# UM_LMA.net
KiCad netlist of a schematic drawn in EAGLE
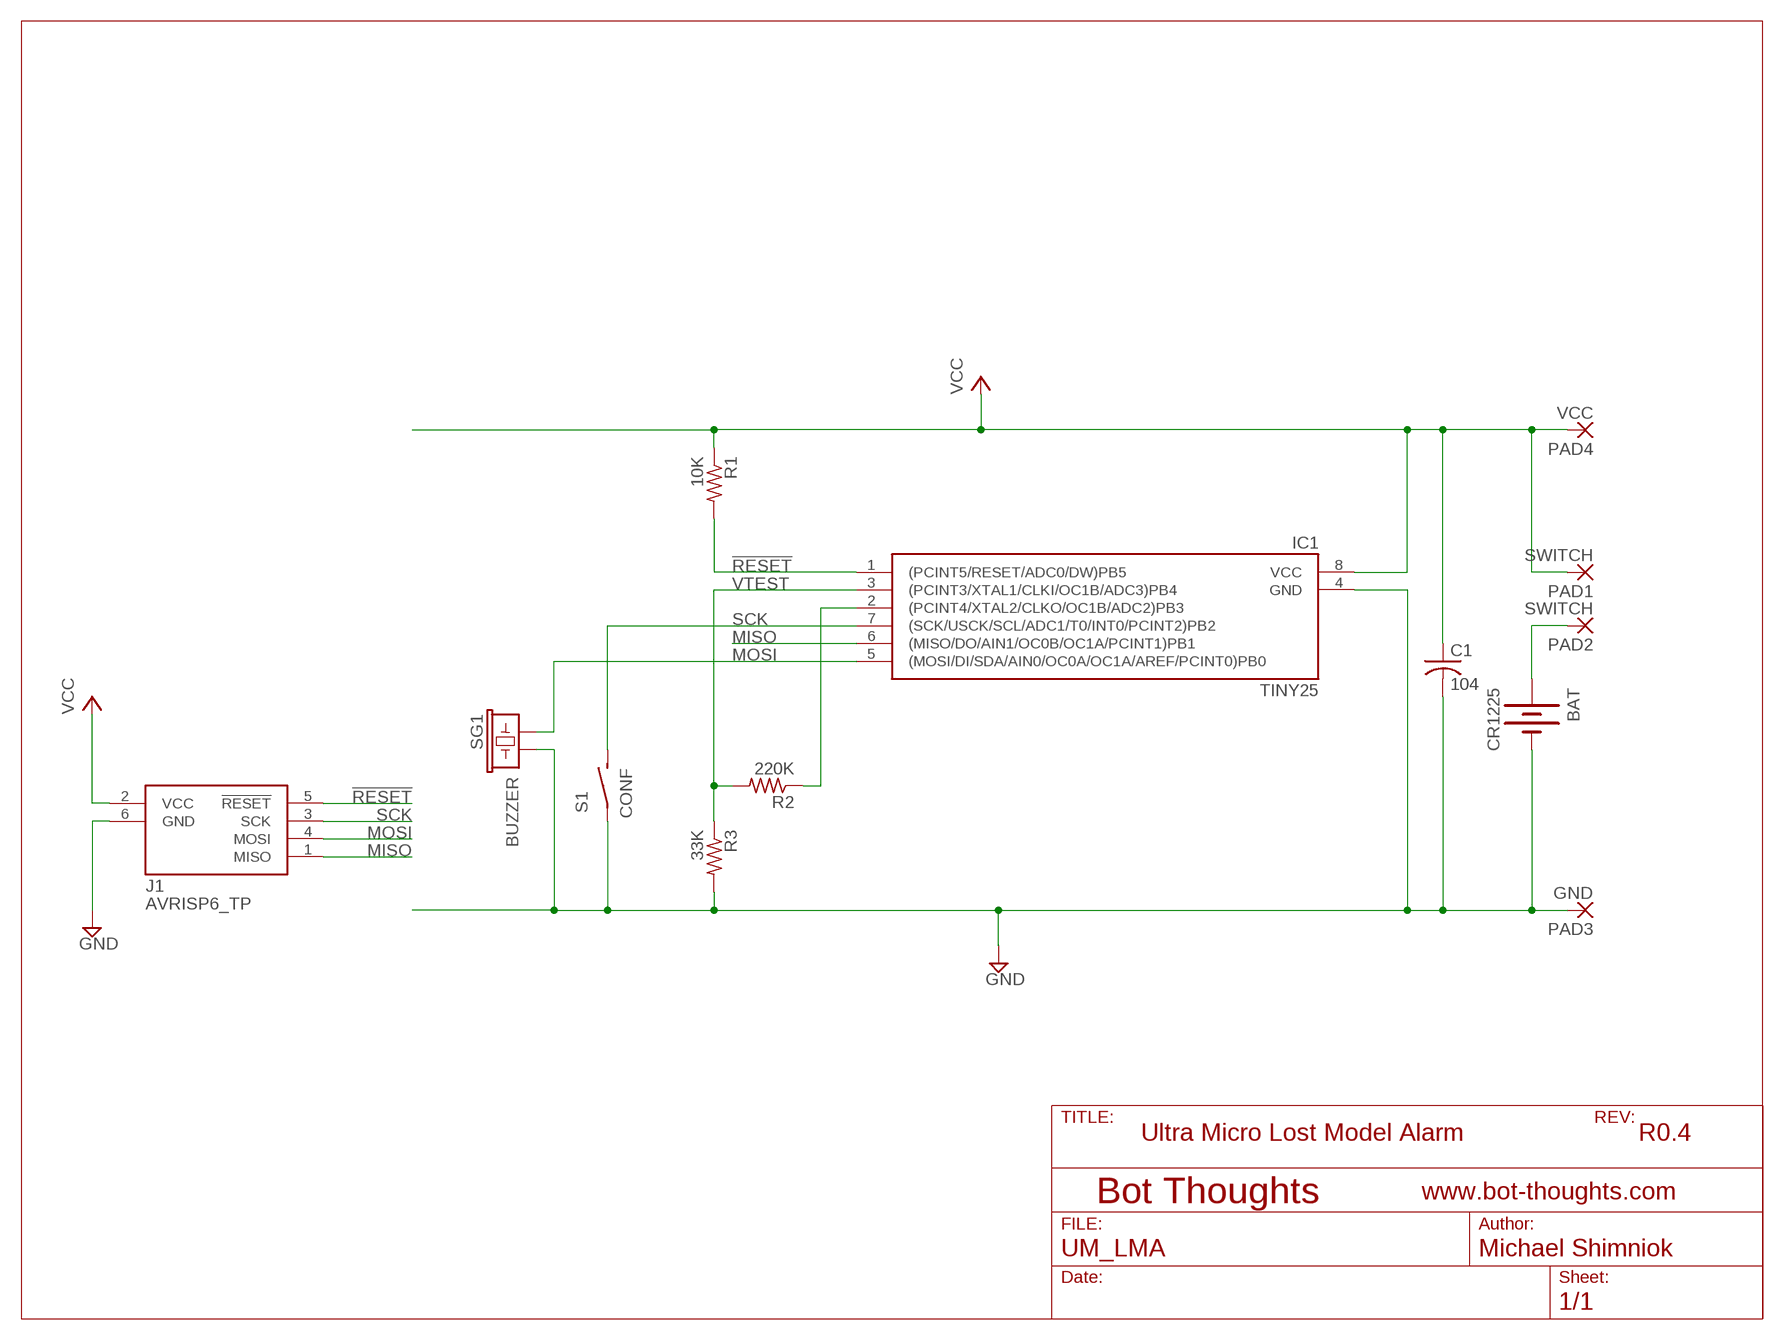
[diagram p0: schematic, sheet 1]

(export (version "E")
  (design (tool "Eeschema 10.0.6"))
  (components
    (comp (ref "BAT")
      (value "CR1225")
      (footprint "eagle-import:BATTCON_12MM_PTH")
      (libsource (lib "eagle-import") (part "BATTERY12PTH"))
    )
    (comp (ref "C1")
      (value "104")
      (footprint "eagle-import:C0603K")
      (fields (field (name "PARTNO") "GRM188R60J105KA01D"))
      (libsource (lib "eagle-import") (part "C-USC0603K"))
    )
    (comp (ref "IC1")
      (value "TINY25")
      (footprint "eagle-import:SOIC8N")
      (libsource (lib "eagle-import") (part "TINY25-20SSU"))
    )
    (comp (ref "J1")
      (value "AVRISP6_TP")
      (footprint "eagle-import:2X3_TP")
      (libsource (lib "eagle-import") (part "AVRISP6_TP"))
    )
    (comp (ref "PAD1")
      (value "SWITCH")
      (footprint "eagle-import:1,6_0,8")
      (libsource (lib "eagle-import") (part "WIREPAD1,6/0,8"))
    )
    (comp (ref "PAD2")
      (value "SWITCH")
      (footprint "eagle-import:1,6_0,8")
      (libsource (lib "eagle-import") (part "WIREPAD1,6/0,8"))
    )
    (comp (ref "PAD3")
      (value "GND")
      (footprint "eagle-import:1,6_0,8")
      (libsource (lib "eagle-import") (part "WIREPAD1,6/0,8"))
    )
    (comp (ref "PAD4")
      (value "VCC")
      (footprint "eagle-import:1,6_0,8")
      (libsource (lib "eagle-import") (part "WIREPAD1,6/0,8"))
    )
    (comp (ref "R1")
      (value "10K")
      (footprint "eagle-import:R0603")
      (fields (field (name "PARTNO") "ERJ-3GEYJ102V"))
      (libsource (lib "eagle-import") (part "R-US_R0603"))
    )
    (comp (ref "R2")
      (value "220K")
      (footprint "eagle-import:R0603")
      (fields (field (name "PARTNO") "ERJ-3GEYJ102V"))
      (libsource (lib "eagle-import") (part "R-US_R0603"))
    )
    (comp (ref "R3")
      (value "33K")
      (footprint "eagle-import:R0603")
      (fields (field (name "PARTNO") "ERJ-3GEYJ102V"))
      (libsource (lib "eagle-import") (part "R-US_R0603"))
    )
    (comp (ref "S1")
      (value "CONF")
      (footprint "eagle-import:3X4X2TACT")
      (libsource (lib "eagle-import") (part "SPST_3X4X2"))
    )
    (comp (ref "SG1")
      (value "BUZZER")
      (footprint "eagle-import:BUZZER_14MM_V_PTH")
      (fields (field (name "PARTNO") "AT-1438-TWT-R"))
      (libsource (lib "eagle-import") (part "BUZZER-AT-1438-TWT-R-VERT"))
    )
  )
  (nets
    (net (code "1") (name "/MISO") (class "Default")
      (node (ref "IC1") (pin "6") (pinfunction "(MISO/DO/AIN1/OC0B/OC1A/PCINT1)PB1_6") (pintype "bidirectional"))
      (node (ref "J1") (pin "1") (pinfunction "MISO_1") (pintype "input"))
    )
    (net (code "2") (name "/MOSI") (class "Default")
      (node (ref "IC1") (pin "5") (pinfunction "(MOSI/DI/SDA/AIN0/OC0A/OC1A/AREF/PCINT0)PB0_5") (pintype "bidirectional"))
      (node (ref "J1") (pin "4") (pinfunction "MOSI_4") (pintype "output"))
      (node (ref "SG1") (pin "P$5") (pinfunction "1_P$5") (pintype "passive"))
    )
    (net (code "3") (name "/SCK") (class "Default")
      (node (ref "IC1") (pin "7") (pinfunction "(SCK/USCK/SCL/ADC1/T0/INT0/PCINT2)PB2_7") (pintype "bidirectional"))
      (node (ref "J1") (pin "3") (pinfunction "SCK_3") (pintype "output"))
      (node (ref "S1") (pin "P$2") (pinfunction "S_P$2") (pintype "passive"))
    )
    (net (code "4") (name "/VTEST") (class "Default")
      (node (ref "IC1") (pin "3") (pinfunction "(PCINT3/XTAL1/CLKI/OC1B/ADC3)PB4_3") (pintype "bidirectional"))
      (node (ref "R2") (pin "2") (pinfunction "2_2") (pintype "passive"))
      (node (ref "R3") (pin "1") (pinfunction "1_1") (pintype "passive"))
    )
    (net (code "5") (name "/~{RESET}") (class "Default")
      (node (ref "IC1") (pin "1") (pinfunction "(PCINT5/RESET/ADC0/DW)PB5_1") (pintype "bidirectional"))
      (node (ref "J1") (pin "5") (pinfunction "~{RESET}_5") (pintype "output"))
      (node (ref "R1") (pin "2") (pinfunction "2_2") (pintype "passive"))
    )
    (net (code "6") (name "GND") (class "Default")
      (node (ref "BAT") (pin "GND") (pinfunction "-_GND") (pintype "power_in"))
      (node (ref "C1") (pin "2") (pinfunction "2_2") (pintype "passive"))
      (node (ref "IC1") (pin "4") (pinfunction "GND_4") (pintype "power_in"))
      (node (ref "J1") (pin "6") (pinfunction "GND_6") (pintype "power_in"))
      (node (ref "PAD3") (pin "1") (pinfunction "P_1") (pintype "passive"))
      (node (ref "R3") (pin "2") (pinfunction "2_2") (pintype "passive"))
      (node (ref "S1") (pin "P$1") (pinfunction "P_P$1") (pintype "passive"))
      (node (ref "SG1") (pin "P$6") (pinfunction "2_P$6") (pintype "passive"))
    )
    (net (code "7") (name "Net-(BAT-+)") (class "Default")
      (node (ref "BAT") (pin "VCC@1") (pinfunction "+_VCC@1") (pintype "power_in"))
      (node (ref "PAD2") (pin "1") (pinfunction "P_1") (pintype "passive"))
    )
    (net (code "8") (name "Net-(IC1-(PCINT4{slash}XTAL2{slash}CLKO{slash}OC1B{slash}ADC2)PB3)") (class "Default")
      (node (ref "IC1") (pin "2") (pinfunction "(PCINT4/XTAL2/CLKO/OC1B/ADC2)PB3_2") (pintype "bidirectional"))
      (node (ref "R2") (pin "1") (pinfunction "1_1") (pintype "passive"))
    )
    (net (code "9") (name "VCC") (class "Default")
      (node (ref "C1") (pin "1") (pinfunction "1_1") (pintype "passive"))
      (node (ref "IC1") (pin "8") (pinfunction "VCC_8") (pintype "power_in"))
      (node (ref "J1") (pin "2") (pinfunction "VCC_2") (pintype "power_in"))
      (node (ref "PAD1") (pin "1") (pinfunction "P_1") (pintype "passive"))
      (node (ref "PAD4") (pin "1") (pinfunction "P_1") (pintype "passive"))
      (node (ref "R1") (pin "1") (pinfunction "1_1") (pintype "passive"))
    )
  )
)
